# Layout_Weather_Station_VX.net
KiCad netlist of a schematic drawn in EAGLE
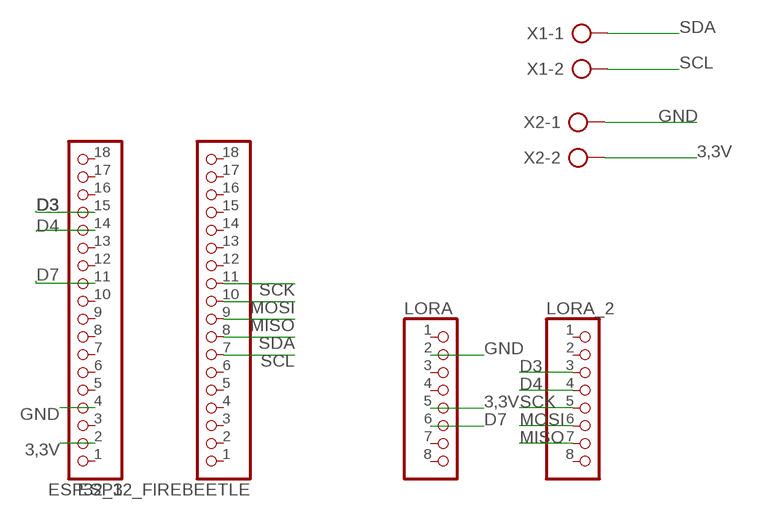
[diagram p0: schematic, sheet 1]

(export (version "E")
  (design (tool "Eeschema 10.0.6"))
  (components
    (comp (ref "ESP32_1")
      (value "PINHD-1X18")
      (footprint "eagle-import:1X18")
      (libsource (lib "eagle-import") (part "PINHD-1X18"))
    )
    (comp (ref "ESP32_FIREBEETLE")
      (value "PINHD-1X18")
      (footprint "eagle-import:1X18")
      (libsource (lib "eagle-import") (part "PINHD-1X18"))
    )
    (comp (ref "LORA")
      (value "PINHD-1X8")
      (footprint "eagle-import:1X08")
      (libsource (lib "eagle-import") (part "PINHD-1X8"))
    )
    (comp (ref "LORA_2")
      (value "PINHD-1X8")
      (footprint "eagle-import:1X08")
      (libsource (lib "eagle-import") (part "PINHD-1X8"))
    )
    (comp (ref "X1")
      (value "AK300/2")
      (footprint "eagle-import:AK300_2")
      (libsource (lib "eagle-import") (part "AK300/2"))
    )
    (comp (ref "X2")
      (value "AK300/2")
      (footprint "eagle-import:AK300_2")
      (libsource (lib "eagle-import") (part "AK300/2"))
    )
  )
  (nets
    (net (code "1") (name "/3,3V") (class "Default")
      (node (ref "ESP32_1") (pin "2") (pinfunction "2_2") (pintype "passive"))
      (node (ref "LORA") (pin "5") (pinfunction "5_5") (pintype "passive"))
      (node (ref "X2") (pin "2") (pinfunction "KL_2") (pintype "passive"))
    )
    (net (code "2") (name "/D3") (class "Default")
      (node (ref "ESP32_1") (pin "15") (pinfunction "15_15") (pintype "passive"))
      (node (ref "LORA_2") (pin "3") (pinfunction "3_3") (pintype "passive"))
    )
    (net (code "3") (name "/D4") (class "Default")
      (node (ref "ESP32_1") (pin "14") (pinfunction "14_14") (pintype "passive"))
      (node (ref "LORA_2") (pin "4") (pinfunction "4_4") (pintype "passive"))
    )
    (net (code "4") (name "/D7") (class "Default")
      (node (ref "ESP32_1") (pin "11") (pinfunction "11_11") (pintype "passive"))
      (node (ref "LORA") (pin "6") (pinfunction "6_6") (pintype "passive"))
    )
    (net (code "5") (name "/GND") (class "Default")
      (node (ref "ESP32_1") (pin "4") (pinfunction "4_4") (pintype "passive"))
      (node (ref "LORA") (pin "2") (pinfunction "2_2") (pintype "passive"))
      (node (ref "X2") (pin "1") (pinfunction "KL_1") (pintype "passive"))
    )
    (net (code "6") (name "/MISO") (class "Default")
      (node (ref "ESP32_FIREBEETLE") (pin "9") (pinfunction "9_9") (pintype "passive"))
      (node (ref "LORA_2") (pin "7") (pinfunction "7_7") (pintype "passive"))
    )
    (net (code "7") (name "/MOSI") (class "Default")
      (node (ref "ESP32_FIREBEETLE") (pin "10") (pinfunction "10_10") (pintype "passive"))
      (node (ref "LORA_2") (pin "6") (pinfunction "6_6") (pintype "passive"))
    )
    (net (code "8") (name "/SCK") (class "Default")
      (node (ref "ESP32_FIREBEETLE") (pin "11") (pinfunction "11_11") (pintype "passive"))
      (node (ref "LORA_2") (pin "5") (pinfunction "5_5") (pintype "passive"))
    )
    (net (code "9") (name "/SCL") (class "Default")
      (node (ref "ESP32_FIREBEETLE") (pin "7") (pinfunction "7_7") (pintype "passive"))
      (node (ref "X1") (pin "2") (pinfunction "KL_2") (pintype "passive"))
    )
    (net (code "10") (name "/SDA") (class "Default")
      (node (ref "ESP32_FIREBEETLE") (pin "8") (pinfunction "8_8") (pintype "passive"))
      (node (ref "X1") (pin "1") (pinfunction "KL_1") (pintype "passive"))
    )
    (net (code "11") (name "unconnected-(ESP32_1-Pad1)") (class "Default")
      (node (ref "ESP32_1") (pin "1") (pinfunction "1_1") (pintype "passive"))
    )
    (net (code "12") (name "unconnected-(ESP32_1-Pad3)") (class "Default")
      (node (ref "ESP32_1") (pin "3") (pinfunction "3_3") (pintype "passive"))
    )
    (net (code "13") (name "unconnected-(ESP32_1-Pad5)") (class "Default")
      (node (ref "ESP32_1") (pin "5") (pinfunction "5_5") (pintype "passive"))
    )
    (net (code "14") (name "unconnected-(ESP32_1-Pad6)") (class "Default")
      (node (ref "ESP32_1") (pin "6") (pinfunction "6_6") (pintype "passive"))
    )
    (net (code "15") (name "unconnected-(ESP32_1-Pad7)") (class "Default")
      (node (ref "ESP32_1") (pin "7") (pinfunction "7_7") (pintype "passive"))
    )
    (net (code "16") (name "unconnected-(ESP32_1-Pad8)") (class "Default")
      (node (ref "ESP32_1") (pin "8") (pinfunction "8_8") (pintype "passive"))
    )
    (net (code "17") (name "unconnected-(ESP32_1-Pad9)") (class "Default")
      (node (ref "ESP32_1") (pin "9") (pinfunction "9_9") (pintype "passive"))
    )
    (net (code "18") (name "unconnected-(ESP32_1-Pad10)") (class "Default")
      (node (ref "ESP32_1") (pin "10") (pinfunction "10_10") (pintype "passive"))
    )
    (net (code "19") (name "unconnected-(ESP32_1-Pad12)") (class "Default")
      (node (ref "ESP32_1") (pin "12") (pinfunction "12_12") (pintype "passive"))
    )
    (net (code "20") (name "unconnected-(ESP32_1-Pad13)") (class "Default")
      (node (ref "ESP32_1") (pin "13") (pinfunction "13_13") (pintype "passive"))
    )
    (net (code "21") (name "unconnected-(ESP32_1-Pad16)") (class "Default")
      (node (ref "ESP32_1") (pin "16") (pinfunction "16_16") (pintype "passive"))
    )
    (net (code "22") (name "unconnected-(ESP32_1-Pad17)") (class "Default")
      (node (ref "ESP32_1") (pin "17") (pinfunction "17_17") (pintype "passive"))
    )
    (net (code "23") (name "unconnected-(ESP32_1-Pad18)") (class "Default")
      (node (ref "ESP32_1") (pin "18") (pinfunction "18_18") (pintype "passive"))
    )
    (net (code "24") (name "unconnected-(ESP32_FIREBEETLE-Pad1)") (class "Default")
      (node (ref "ESP32_FIREBEETLE") (pin "1") (pinfunction "1_1") (pintype "passive"))
    )
    (net (code "25") (name "unconnected-(ESP32_FIREBEETLE-Pad2)") (class "Default")
      (node (ref "ESP32_FIREBEETLE") (pin "2") (pinfunction "2_2") (pintype "passive"))
    )
    (net (code "26") (name "unconnected-(ESP32_FIREBEETLE-Pad3)") (class "Default")
      (node (ref "ESP32_FIREBEETLE") (pin "3") (pinfunction "3_3") (pintype "passive"))
    )
    (net (code "27") (name "unconnected-(ESP32_FIREBEETLE-Pad4)") (class "Default")
      (node (ref "ESP32_FIREBEETLE") (pin "4") (pinfunction "4_4") (pintype "passive"))
    )
    (net (code "28") (name "unconnected-(ESP32_FIREBEETLE-Pad5)") (class "Default")
      (node (ref "ESP32_FIREBEETLE") (pin "5") (pinfunction "5_5") (pintype "passive"))
    )
    (net (code "29") (name "unconnected-(ESP32_FIREBEETLE-Pad6)") (class "Default")
      (node (ref "ESP32_FIREBEETLE") (pin "6") (pinfunction "6_6") (pintype "passive"))
    )
    (net (code "30") (name "unconnected-(ESP32_FIREBEETLE-Pad12)") (class "Default")
      (node (ref "ESP32_FIREBEETLE") (pin "12") (pinfunction "12_12") (pintype "passive"))
    )
    (net (code "31") (name "unconnected-(ESP32_FIREBEETLE-Pad13)") (class "Default")
      (node (ref "ESP32_FIREBEETLE") (pin "13") (pinfunction "13_13") (pintype "passive"))
    )
    (net (code "32") (name "unconnected-(ESP32_FIREBEETLE-Pad14)") (class "Default")
      (node (ref "ESP32_FIREBEETLE") (pin "14") (pinfunction "14_14") (pintype "passive"))
    )
    (net (code "33") (name "unconnected-(ESP32_FIREBEETLE-Pad15)") (class "Default")
      (node (ref "ESP32_FIREBEETLE") (pin "15") (pinfunction "15_15") (pintype "passive"))
    )
    (net (code "34") (name "unconnected-(ESP32_FIREBEETLE-Pad16)") (class "Default")
      (node (ref "ESP32_FIREBEETLE") (pin "16") (pinfunction "16_16") (pintype "passive"))
    )
    (net (code "35") (name "unconnected-(ESP32_FIREBEETLE-Pad17)") (class "Default")
      (node (ref "ESP32_FIREBEETLE") (pin "17") (pinfunction "17_17") (pintype "passive"))
    )
    (net (code "36") (name "unconnected-(ESP32_FIREBEETLE-Pad18)") (class "Default")
      (node (ref "ESP32_FIREBEETLE") (pin "18") (pinfunction "18_18") (pintype "passive"))
    )
    (net (code "37") (name "unconnected-(LORA-Pad1)") (class "Default")
      (node (ref "LORA") (pin "1") (pinfunction "1_1") (pintype "passive"))
    )
    (net (code "38") (name "unconnected-(LORA-Pad3)") (class "Default")
      (node (ref "LORA") (pin "3") (pinfunction "3_3") (pintype "passive"))
    )
    (net (code "39") (name "unconnected-(LORA-Pad4)") (class "Default")
      (node (ref "LORA") (pin "4") (pinfunction "4_4") (pintype "passive"))
    )
    (net (code "40") (name "unconnected-(LORA-Pad7)") (class "Default")
      (node (ref "LORA") (pin "7") (pinfunction "7_7") (pintype "passive"))
    )
    (net (code "41") (name "unconnected-(LORA-Pad8)") (class "Default")
      (node (ref "LORA") (pin "8") (pinfunction "8_8") (pintype "passive"))
    )
    (net (code "42") (name "unconnected-(LORA_2-Pad1)") (class "Default")
      (node (ref "LORA_2") (pin "1") (pinfunction "1_1") (pintype "passive"))
    )
    (net (code "43") (name "unconnected-(LORA_2-Pad2)") (class "Default")
      (node (ref "LORA_2") (pin "2") (pinfunction "2_2") (pintype "passive"))
    )
    (net (code "44") (name "unconnected-(LORA_2-Pad8)") (class "Default")
      (node (ref "LORA_2") (pin "8") (pinfunction "8_8") (pintype "passive"))
    )
  )
)
